# Power.net
KiCad netlist of a schematic drawn in Altium Designer
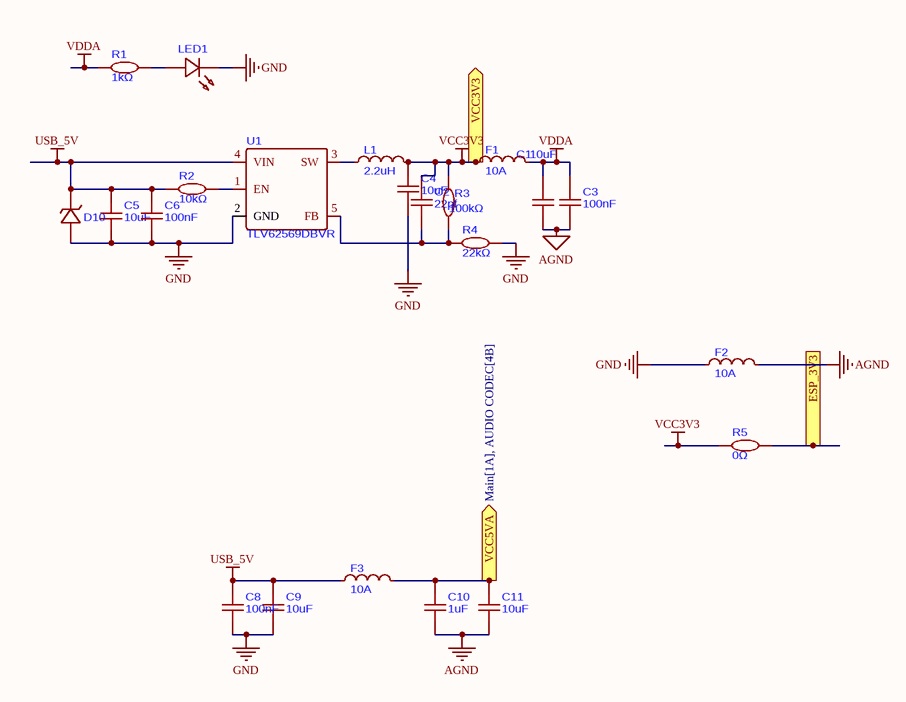
[diagram p0: Power.SchDoc]

(export (version "E")
  (design (tool "Eeschema 10.0.6"))
  (components
    (comp (ref "C1")
      (value "10uF")
      (footprint "C0603")
      (description "25V 10uF X5R ±20% 0603 Ceramic Capacitors ROHS")
      (libsource (lib "Schlib2") (part "CL10A106MA8NRNC"))
    )
    (comp (ref "C2")
      (value "22pf")
      (footprint "C0603")
      (description "50V 22pF C0G ±5% 0603 Ceramic Capacitors RoHS")
      (libsource (lib "Schlib2") (part "CL10C220JB8NNNC"))
    )
    (comp (ref "C3")
      (value "100nF")
      (footprint "C0603")
      (description "50V 100nF X7R ±10% 0603 Ceramic Capacitors ROHS")
      (libsource (lib "Schlib2") (part "CC0603KRX7R9BB104"))
    )
    (comp (ref "C4")
      (value "10uF")
      (footprint "C0603")
      (description "25V 10uF X5R ±20% 0603 Ceramic Capacitors ROHS")
      (libsource (lib "Schlib2") (part "CL10A106MA8NRNC"))
    )
    (comp (ref "C5")
      (value "10uF")
      (footprint "C0603")
      (description "25V 10uF X5R ±20% 0603 Ceramic Capacitors ROHS")
      (libsource (lib "Schlib2") (part "CL10A106MA8NRNC"))
    )
    (comp (ref "C6")
      (value "100nF")
      (footprint "C0603")
      (description "50V 100nF X7R ±10% 0603 Ceramic Capacitors ROHS")
      (libsource (lib "Schlib2") (part "CC0603KRX7R9BB104"))
    )
    (comp (ref "C8")
      (value "100nF")
      (footprint "C0603")
      (description "50V 100nF X7R ±10% 0603 Ceramic Capacitors ROHS")
      (libsource (lib "Schlib2") (part "CC0603KRX7R9BB104"))
    )
    (comp (ref "C9")
      (value "10uF")
      (footprint "C0603")
      (description "25V 10uF X5R ±20% 0603 Ceramic Capacitors ROHS")
      (libsource (lib "Schlib2") (part "CL10A106MA8NRNC"))
    )
    (comp (ref "C10")
      (value "1uF")
      (footprint "C0603")
      (description "25V 1uF X7R ±10% 0603 Ceramic Capacitors ROHS")
      (libsource (lib "Schlib2") (part "CL10B105KA8NNNC"))
    )
    (comp (ref "C11")
      (value "10uF")
      (footprint "C0603")
      (description "25V 10uF X5R ±20% 0603 Ceramic Capacitors ROHS")
      (libsource (lib "Schlib2") (part "CL10A106MA8NRNC"))
    )
    (comp (ref "D10")
      (value "DIODE ZENER 5.6V 500mW LL-34")
      (footprint "LL-34_L3.5-W1.5-RD")
      (description "Zener Diode Independent 5.6V 500mW Surface Mount LL-34")
      (libsource (lib "Schlib2") (part "ZMM5V6_C707195"))
    )
    (comp (ref "F1")
      (value "10A")
      (footprint "IND-SMD_L8.5-W3.1")
      (description "4mΩ 100Ω@100MHz SMD,8.5x3.1mm Ferrite Beads and Chips ROHS")
      (libsource (lib "Schlib2") (part "HI3312X101R-10"))
    )
    (comp (ref "F2")
      (value "10A")
      (footprint "IND-SMD_L8.5-W3.1")
      (description "4mΩ 100Ω@100MHz SMD,8.5x3.1mm Ferrite Beads and Chips ROHS")
      (libsource (lib "Schlib2") (part "HI3312X101R-10"))
    )
    (comp (ref "F3")
      (value "10A")
      (footprint "IND-SMD_L8.5-W3.1")
      (description "4mΩ 100Ω@100MHz SMD,8.5x3.1mm Ferrite Beads and Chips ROHS")
      (libsource (lib "Schlib2") (part "HI3312X101R-10"))
    )
    (comp (ref "L1")
      (value "2.2uH")
      (footprint "IND-SMD_L5.4-W5.2")
      (description "7A 2.2uH Molded Inductor ±20% 7A 29mΩ SMD,5.4x5.2mm Fixed Inductors RoHS")
      (libsource (lib "Schlib2") (part "APH0530T2R2M"))
    )
    (comp (ref "LED1")
      (value "XL-1608SURC-06")
      (footprint "LED0603-RD_RED")
      (description "20mA 2.3V Red 50mW 0603 LED Indication - Discrete ROHS")
      (libsource (lib "Schlib2") (part "XL-1608SURC-06"))
    )
    (comp (ref "R1")
      (value "1kΩ")
      (footprint "R0603")
      (description "100mW 1kΩ 50V ±100ppm/℃ Thick Film Resistor ±5% 0603 Chip Resistor - Surface Mount ROHS")
      (libsource (lib "Schlib2") (part "RMC 0603 1K J N"))
    )
    (comp (ref "R2")
      (value "10kΩ")
      (footprint "R0603")
      (description "100mW 10kΩ 75V ±100ppm/℃ Thick Film Resistor ±1% 0603 Chip Resistor - Surface Mount ROHS")
      (libsource (lib "Schlib2") (part "RC0603FR-0710KL"))
    )
    (comp (ref "R3")
      (value "100kΩ")
      (footprint "R0603")
      (description "100mW 100kΩ 75V ±100ppm/℃ Thick Film Resistor ±1% 0603 Chip Resistor - Surface Mount ROHS")
      (libsource (lib "Schlib2") (part "RC0603FR-07100KL"))
    )
    (comp (ref "R4")
      (value "22kΩ")
      (footprint "R0603")
      (description "100mW 22kΩ 75V ±100ppm/℃ Thick Film Resistor ±1% 0603 Chip Resistor - Surface Mount RoHS")
      (libsource (lib "Schlib2") (part "RC0603FR-0722KL"))
    )
    (comp (ref "R5")
      (value "0Ω")
      (footprint "R0603")
      (description "100mW 0Ω 75V Thick Film Resistor ±5% 0603 Chip Resistor - Surface Mount RoHS")
      (libsource (lib "Schlib2") (part "RC0603JR-070RL"))
    )
    (comp (ref "U1")
      (value "TLV62569DBVR")
      (footprint "SOT-23-5_L3.0-W1.7-P0.95-LS2.8-BR")
      (libsource (lib "Schlib2") (part "TLV62569DBVR"))
    )
  )
  (nets
    (net (code "1") (name "/ESP_3V3") (class "Default")
      (node (ref "R5") (pin "2") (pinfunction "2_2") (pintype "passive"))
    )
    (net (code "2") (name "/VCC5VA") (class "Default")
      (node (ref "C10") (pin "1") (pinfunction "1_1") (pintype "passive"))
      (node (ref "C11") (pin "2") (pinfunction "2_2") (pintype "passive"))
      (node (ref "F3") (pin "2") (pinfunction "2_2") (pintype "passive"))
    )
    (net (code "3") (name "AGND") (class "Default")
      (node (ref "C1") (pin "1") (pinfunction "1_1") (pintype "passive"))
      (node (ref "C10") (pin "2") (pinfunction "2_2") (pintype "passive"))
      (node (ref "C11") (pin "1") (pinfunction "1_1") (pintype "passive"))
      (node (ref "C3") (pin "1") (pinfunction "1_1") (pintype "passive"))
      (node (ref "F2") (pin "2") (pinfunction "2_2") (pintype "passive"))
    )
    (net (code "4") (name "GND") (class "Default")
      (node (ref "C4") (pin "1") (pinfunction "1_1") (pintype "passive"))
      (node (ref "C5") (pin "1") (pinfunction "1_1") (pintype "passive"))
      (node (ref "C6") (pin "1") (pinfunction "1_1") (pintype "passive"))
      (node (ref "C8") (pin "1") (pinfunction "1_1") (pintype "passive"))
      (node (ref "C9") (pin "1") (pinfunction "1_1") (pintype "passive"))
      (node (ref "D10") (pin "2") (pinfunction "A_2") (pintype "passive"))
      (node (ref "F2") (pin "1") (pinfunction "1_1") (pintype "passive"))
      (node (ref "LED1") (pin "1") (pinfunction "K_1") (pintype "passive"))
      (node (ref "R4") (pin "2") (pinfunction "2_2") (pintype "passive"))
      (node (ref "U1") (pin "2") (pinfunction "GND_2") (pintype "passive"))
    )
    (net (code "5") (name "Net-(LED1-A)") (class "Default")
      (node (ref "LED1") (pin "2") (pinfunction "A_2") (pintype "passive"))
      (node (ref "R1") (pin "1") (pinfunction "1_1") (pintype "passive"))
    )
    (net (code "6") (name "Net-(U1-EN)") (class "Default")
      (node (ref "R2") (pin "2") (pinfunction "2_2") (pintype "passive"))
      (node (ref "U1") (pin "1") (pinfunction "EN_1") (pintype "passive"))
    )
    (net (code "7") (name "Net-(U1-FB)") (class "Default")
      (node (ref "C2") (pin "1") (pinfunction "1_1") (pintype "passive"))
      (node (ref "R3") (pin "1") (pinfunction "1_1") (pintype "passive"))
      (node (ref "R4") (pin "1") (pinfunction "1_1") (pintype "passive"))
      (node (ref "U1") (pin "5") (pinfunction "FB_5") (pintype "passive"))
    )
    (net (code "8") (name "Net-(U1-SW)") (class "Default")
      (node (ref "L1") (pin "1") (pinfunction "1_1") (pintype "passive"))
      (node (ref "U1") (pin "3") (pinfunction "SW_3") (pintype "passive"))
    )
    (net (code "9") (name "USB_5V") (class "Default")
      (node (ref "C5") (pin "2") (pinfunction "2_2") (pintype "passive"))
      (node (ref "C6") (pin "2") (pinfunction "2_2") (pintype "passive"))
      (node (ref "C8") (pin "2") (pinfunction "2_2") (pintype "passive"))
      (node (ref "C9") (pin "2") (pinfunction "2_2") (pintype "passive"))
      (node (ref "D10") (pin "1") (pinfunction "K_1") (pintype "passive"))
      (node (ref "F3") (pin "1") (pinfunction "1_1") (pintype "passive"))
      (node (ref "R2") (pin "1") (pinfunction "1_1") (pintype "passive"))
      (node (ref "U1") (pin "4") (pinfunction "VIN_4") (pintype "passive"))
    )
    (net (code "10") (name "VCC3V3") (class "Default")
      (node (ref "C2") (pin "2") (pinfunction "2_2") (pintype "passive"))
      (node (ref "C4") (pin "2") (pinfunction "2_2") (pintype "passive"))
      (node (ref "F1") (pin "1") (pinfunction "1_1") (pintype "passive"))
      (node (ref "L1") (pin "2") (pinfunction "2_2") (pintype "passive"))
      (node (ref "R3") (pin "2") (pinfunction "2_2") (pintype "passive"))
      (node (ref "R5") (pin "1") (pinfunction "1_1") (pintype "passive"))
    )
    (net (code "11") (name "VDDA") (class "Default")
      (node (ref "C1") (pin "2") (pinfunction "2_2") (pintype "passive"))
      (node (ref "C3") (pin "2") (pinfunction "2_2") (pintype "passive"))
      (node (ref "F1") (pin "2") (pinfunction "2_2") (pintype "passive"))
      (node (ref "R1") (pin "2") (pinfunction "2_2") (pintype "passive"))
    )
  )
)
